# 7_Power_Supply.net
KiCad netlist of a schematic drawn in Altium Designer
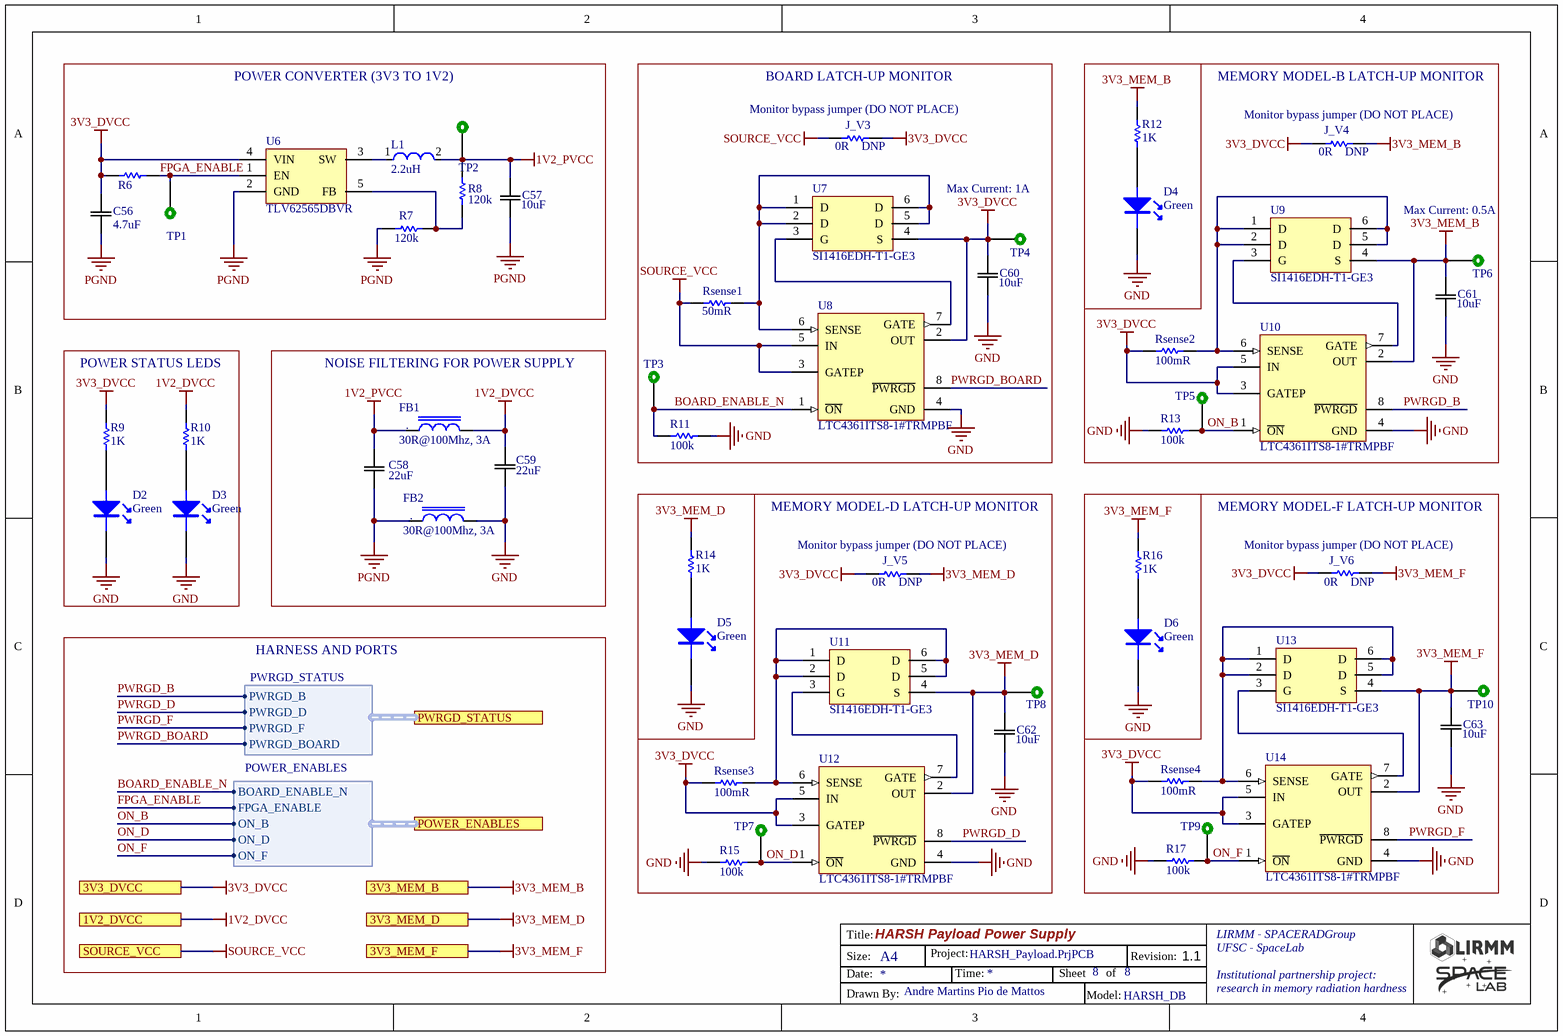
[diagram p0: 7_Power_Supply.SchDoc]

(export (version "E")
  (design (tool "Eeschema 10.0.6"))
  (components
    (comp (ref "C56")
      (value "4.7uF")
      (footprint "DONE_C0603")
      (description "CAP CER 4.7UF 10V 10% X5R 0603")
      (fields (field (name "PARTNUMBER") "C0603C475K8PACTU") (field (name "VOLTAGE") "10V"))
      (libsource (lib "HARSH_Payload_SchLib") (part "DONE_CAP_4.7uF_0603_X5R"))
    )
    (comp (ref "C57")
      (value "10uF")
      (footprint "DONE_C0603")
      (description "CAP CER 10uF 16V 0603 X5R")
      (fields
        (field (name "PARTNUMBER") "GRM188R61C106KAALD")
        (field (name "MANUFACTURER") "Murata")
        (field (name "CAPACITANCE") "10uF")
      )
      (libsource (lib "HARSH_Payload_SchLib") (part "DONE_CAP_10uF_0603_X5R"))
    )
    (comp (ref "C58")
      (value "22uF")
      (footprint "DONE_C0603")
      (description "CAP CER 22UF 10V X5R 0603")
      (fields (field (name "PARTNUMBER") "CL10A226MPCNUBE") (field (name "CAPACITANCE") "22uF"))
      (libsource (lib "HARSH_Payload_SchLib") (part "DONE_CAP_22uF_0603_X5R"))
    )
    (comp (ref "C59")
      (value "22uF")
      (footprint "DONE_C0603")
      (description "CAP CER 22UF 10V X5R 0603")
      (fields (field (name "PARTNUMBER") "CL10A226MPCNUBE") (field (name "CAPACITANCE") "22uF"))
      (libsource (lib "HARSH_Payload_SchLib") (part "DONE_CAP_22uF_0603_X5R"))
    )
    (comp (ref "C60")
      (value "10uF")
      (footprint "DONE_C0603")
      (description "CAP CER 10uF 16V 0603 X5R")
      (fields
        (field (name "PARTNUMBER") "GRM188R61C106KAALD")
        (field (name "MANUFACTURER") "Murata")
        (field (name "CAPACITANCE") "10uF")
      )
      (libsource (lib "HARSH_Payload_SchLib") (part "DONE_CAP_10uF_0603_X5R"))
    )
    (comp (ref "C61")
      (value "10uF")
      (footprint "DONE_C0603")
      (description "CAP CER 10uF 16V 0603 X5R")
      (fields
        (field (name "PARTNUMBER") "GRM188R61C106KAALD")
        (field (name "MANUFACTURER") "Murata")
        (field (name "CAPACITANCE") "10uF")
      )
      (libsource (lib "HARSH_Payload_SchLib") (part "DONE_CAP_10uF_0603_X5R"))
    )
    (comp (ref "C62")
      (value "10uF")
      (footprint "DONE_C0603")
      (description "CAP CER 10uF 16V 0603 X5R")
      (fields
        (field (name "PARTNUMBER") "GRM188R61C106KAALD")
        (field (name "MANUFACTURER") "Murata")
        (field (name "CAPACITANCE") "10uF")
      )
      (libsource (lib "HARSH_Payload_SchLib") (part "DONE_CAP_10uF_0603_X5R"))
    )
    (comp (ref "C63")
      (value "10uF")
      (footprint "DONE_C0603")
      (description "CAP CER 10uF 16V 0603 X5R")
      (fields
        (field (name "PARTNUMBER") "GRM188R61C106KAALD")
        (field (name "MANUFACTURER") "Murata")
        (field (name "CAPACITANCE") "10uF")
      )
      (libsource (lib "HARSH_Payload_SchLib") (part "DONE_CAP_10uF_0603_X5R"))
    )
    (comp (ref "D2")
      (value "Green")
      (footprint "DONE_D0603_GREEN")
      (description "SMD Green LED")
      (fields (field (name "PARTNUMBER") "HSMQ-C191-T0000"))
      (libsource (lib "HARSH_Payload_SchLib") (part "DONE_LED_GREEN_0603"))
    )
    (comp (ref "D3")
      (value "Green")
      (footprint "DONE_D0603_GREEN")
      (description "SMD Green LED")
      (fields (field (name "PARTNUMBER") "HSMQ-C191-T0000"))
      (libsource (lib "HARSH_Payload_SchLib") (part "DONE_LED_GREEN_0603"))
    )
    (comp (ref "D4")
      (value "Green")
      (footprint "DONE_D0603_GREEN")
      (description "SMD Green LED")
      (fields (field (name "PARTNUMBER") "HSMQ-C191-T0000"))
      (libsource (lib "HARSH_Payload_SchLib") (part "DONE_LED_GREEN_0603"))
    )
    (comp (ref "D5")
      (value "Green")
      (footprint "DONE_D0603_GREEN")
      (description "SMD Green LED")
      (fields (field (name "PARTNUMBER") "HSMQ-C191-T0000"))
      (libsource (lib "HARSH_Payload_SchLib") (part "DONE_LED_GREEN_0603"))
    )
    (comp (ref "D6")
      (value "Green")
      (footprint "DONE_D0603_GREEN")
      (description "SMD Green LED")
      (fields (field (name "PARTNUMBER") "HSMQ-C191-T0000"))
      (libsource (lib "HARSH_Payload_SchLib") (part "DONE_LED_GREEN_0603"))
    )
    (comp (ref "FB1")
      (value "30R@100Mhz, 3A")
      (footprint "DONE_L0805")
      (description "Ferrite Bead 30 OHM 3A 100MHz")
      (fields (field (name "PARTNUMBER") "BLM21PG300SN1D"))
      (libsource (lib "HARSH_Payload_SchLib") (part "DONE_FB_30R_3A_100MHz_0805"))
    )
    (comp (ref "FB2")
      (value "30R@100Mhz, 3A")
      (footprint "DONE_L0805")
      (description "Ferrite Bead 30 OHM 3A 100MHz")
      (fields (field (name "PARTNUMBER") "BLM21PG300SN1D"))
      (libsource (lib "HARSH_Payload_SchLib") (part "DONE_FB_30R_3A_100MHz_0805"))
    )
    (comp (ref "J_V3")
      (value "0R")
      (footprint "DONE_R0603")
      (description "RES SMD 0 OHM JUMPER 1/10W 0603")
      (fields (field (name "PARTNUMBER") "RC0603JR-070RL"))
      (libsource (lib "HARSH_Payload_SchLib") (part "DONE_RES_0R_0603"))
    )
    (comp (ref "J_V4")
      (value "0R")
      (footprint "DONE_R0603")
      (description "RES SMD 0 OHM JUMPER 1/10W 0603")
      (fields (field (name "PARTNUMBER") "RC0603JR-070RL"))
      (libsource (lib "HARSH_Payload_SchLib") (part "DONE_RES_0R_0603"))
    )
    (comp (ref "J_V5")
      (value "0R")
      (footprint "DONE_R0603")
      (description "RES SMD 0 OHM JUMPER 1/10W 0603")
      (fields (field (name "PARTNUMBER") "RC0603JR-070RL"))
      (libsource (lib "HARSH_Payload_SchLib") (part "DONE_RES_0R_0603"))
    )
    (comp (ref "J_V6")
      (value "0R")
      (footprint "DONE_R0603")
      (description "RES SMD 0 OHM JUMPER 1/10W 0603")
      (fields (field (name "PARTNUMBER") "RC0603JR-070RL"))
      (libsource (lib "HARSH_Payload_SchLib") (part "DONE_RES_0R_0603"))
    )
    (comp (ref "L1")
      (value "2.2uH")
      (footprint "DONE_IND_2.2uH")
      (description "Inductor Power Chip Shielded Wirewound 2.2uH 20% 1MHz Ferrite 1.8A 0.0588Ohm DCR 1515 T/R")
      (fields (field (name "PARTNUMBER") "LQH44PN2R2MP0L") (field (name "Comment") "DONE_IND_2.2uH"))
      (libsource (lib "HARSH_Payload_SchLib") (part "DONE_IND_2.2uH"))
    )
    (comp (ref "R6")
      (value "10k")
      (footprint "DONE_R0603")
      (description "1/8W 1%  0603 10K")
      (fields
        (field (name "PARTNUMBER") "MCT0603MC1002FP500")
        (field (name "MANUFACTURER") "Vishay Beyschlag")
      )
      (libsource (lib "HARSH_Payload_SchLib") (part "DONE_RES_10K_0603"))
    )
    (comp (ref "R7")
      (value "120k")
      (footprint "DONE_R0603")
      (description "1/10W 1%  0603")
      (fields
        (field (name "PARTNUMBER") "CRCW0603120KFKEAC")
        (field (name "MANUFACTURER") "Vishay Beyschlag")
        (field (name "RESISTANCE") "120k")
      )
      (libsource (lib "HARSH_Payload_SchLib") (part "DONE_RES_120K_0603"))
    )
    (comp (ref "R8")
      (value "120k")
      (footprint "DONE_R0603")
      (description "1/10W 1%  0603")
      (fields
        (field (name "PARTNUMBER") "CRCW0603120KFKEAC")
        (field (name "MANUFACTURER") "Vishay Beyschlag")
        (field (name "RESISTANCE") "120k")
      )
      (libsource (lib "HARSH_Payload_SchLib") (part "DONE_RES_120K_0603"))
    )
    (comp (ref "R9")
      (value "1K")
      (footprint "DONE_R0603")
      (description "RES SMD 1K OHM 1% 1/4W 0603")
      (fields
        (field (name "MANUFACTURER") "Rohm")
        (field (name "MANUFACTURER PART NUMBER") "ESR03EZPF1001")
        (field (name "RESISTANCE") "1K")
      )
      (libsource (lib "HARSH_Payload_SchLib") (part "DONE_RES_1K_0603"))
    )
    (comp (ref "R10")
      (value "1K")
      (footprint "DONE_R0603")
      (description "RES SMD 1K OHM 1% 1/4W 0603")
      (fields
        (field (name "MANUFACTURER") "Rohm")
        (field (name "MANUFACTURER PART NUMBER") "ESR03EZPF1001")
        (field (name "RESISTANCE") "1K")
      )
      (libsource (lib "HARSH_Payload_SchLib") (part "DONE_RES_1K_0603"))
    )
    (comp (ref "R11")
      (value "100k")
      (footprint "DONE_R0805")
      (description "RES 100K OHM 1/8W 1% 0805")
      (fields
        (field (name "PARTNUMBER") "AC0805FR-13100KL")
        (field (name "MANUFACTURER") "Yageo")
        (field (name "RESISTANCE") "100k")
      )
      (libsource (lib "HARSH_Payload_SchLib") (part "DONE_RES_100k_0805"))
    )
    (comp (ref "R12")
      (value "1K")
      (footprint "DONE_R0603")
      (description "RES SMD 1K OHM 1% 1/4W 0603")
      (fields
        (field (name "MANUFACTURER") "Rohm")
        (field (name "MANUFACTURER PART NUMBER") "ESR03EZPF1001")
        (field (name "RESISTANCE") "1K")
      )
      (libsource (lib "HARSH_Payload_SchLib") (part "DONE_RES_1K_0603"))
    )
    (comp (ref "R13")
      (value "100k")
      (footprint "DONE_R0805")
      (description "RES 100K OHM 1/8W 1% 0805")
      (fields
        (field (name "PARTNUMBER") "AC0805FR-13100KL")
        (field (name "MANUFACTURER") "Yageo")
        (field (name "RESISTANCE") "100k")
      )
      (libsource (lib "HARSH_Payload_SchLib") (part "DONE_RES_100k_0805"))
    )
    (comp (ref "R14")
      (value "1K")
      (footprint "DONE_R0603")
      (description "RES SMD 1K OHM 1% 1/4W 0603")
      (fields
        (field (name "MANUFACTURER") "Rohm")
        (field (name "MANUFACTURER PART NUMBER") "ESR03EZPF1001")
        (field (name "RESISTANCE") "1K")
      )
      (libsource (lib "HARSH_Payload_SchLib") (part "DONE_RES_1K_0603"))
    )
    (comp (ref "R15")
      (value "100k")
      (footprint "DONE_R0805")
      (description "RES 100K OHM 1/8W 1% 0805")
      (fields
        (field (name "PARTNUMBER") "AC0805FR-13100KL")
        (field (name "MANUFACTURER") "Yageo")
        (field (name "RESISTANCE") "100k")
      )
      (libsource (lib "HARSH_Payload_SchLib") (part "DONE_RES_100k_0805"))
    )
    (comp (ref "R16")
      (value "1K")
      (footprint "DONE_R0603")
      (description "RES SMD 1K OHM 1% 1/4W 0603")
      (fields
        (field (name "MANUFACTURER") "Rohm")
        (field (name "MANUFACTURER PART NUMBER") "ESR03EZPF1001")
        (field (name "RESISTANCE") "1K")
      )
      (libsource (lib "HARSH_Payload_SchLib") (part "DONE_RES_1K_0603"))
    )
    (comp (ref "R17")
      (value "100k")
      (footprint "DONE_R0805")
      (description "RES 100K OHM 1/8W 1% 0805")
      (fields
        (field (name "PARTNUMBER") "AC0805FR-13100KL")
        (field (name "MANUFACTURER") "Yageo")
        (field (name "RESISTANCE") "100k")
      )
      (libsource (lib "HARSH_Payload_SchLib") (part "DONE_RES_100k_0805"))
    )
    (comp (ref "Rsense1")
      (value "0.05R")
      (footprint "DONE_R0603")
      (description "RES 0.05 OHM 1% 1/3W 0603")
      (fields (field (name "PARTNUMBER") "ERJ-3BWFR050V") (field (name "RESISTANCE") "50mR"))
      (libsource (lib "HARSH_Payload_SchLib") (part "DONE_RES_0.05R_0603"))
    )
    (comp (ref "Rsense2")
      (value "0.1")
      (footprint "DONE_R0603")
      (description "RES 100 OHM 1% 1/8W 0603")
      (fields (field (name "RESISTANCE") "100mR") (field (name "PARTNUMBER") "RNCP0603FTD100R"))
      (libsource (lib "HARSH_Payload_SchLib") (part "DONE_RES_0.1R_0603"))
    )
    (comp (ref "Rsense3")
      (value "0.1")
      (footprint "DONE_R0603")
      (description "RES 100 OHM 1% 1/8W 0603")
      (fields (field (name "RESISTANCE") "100mR") (field (name "PARTNUMBER") "RNCP0603FTD100R"))
      (libsource (lib "HARSH_Payload_SchLib") (part "DONE_RES_0.1R_0603"))
    )
    (comp (ref "Rsense4")
      (value "0.1")
      (footprint "DONE_R0603")
      (description "RES 100 OHM 1% 1/8W 0603")
      (fields (field (name "RESISTANCE") "100mR") (field (name "PARTNUMBER") "RNCP0603FTD100R"))
      (libsource (lib "HARSH_Payload_SchLib") (part "DONE_RES_0.1R_0603"))
    )
    (comp (ref "TP1")
      (value "TEST_POINT")
      (footprint "DONE_TEST_POINT")
      (description "Test point")
      (libsource (lib "HARSH_Payload_SchLib") (part "DONE_TEST_POINT"))
    )
    (comp (ref "TP2")
      (value "TEST_POINT")
      (footprint "DONE_TEST_POINT")
      (description "Test point")
      (libsource (lib "HARSH_Payload_SchLib") (part "DONE_TEST_POINT"))
    )
    (comp (ref "TP3")
      (value "TEST_POINT")
      (footprint "DONE_TEST_POINT")
      (description "Test point")
      (libsource (lib "HARSH_Payload_SchLib") (part "DONE_TEST_POINT"))
    )
    (comp (ref "TP4")
      (value "TEST_POINT")
      (footprint "DONE_TEST_POINT")
      (description "Test point")
      (libsource (lib "HARSH_Payload_SchLib") (part "DONE_TEST_POINT"))
    )
    (comp (ref "TP5")
      (value "TEST_POINT")
      (footprint "DONE_TEST_POINT")
      (description "Test point")
      (libsource (lib "HARSH_Payload_SchLib") (part "DONE_TEST_POINT"))
    )
    (comp (ref "TP6")
      (value "TEST_POINT")
      (footprint "DONE_TEST_POINT")
      (description "Test point")
      (libsource (lib "HARSH_Payload_SchLib") (part "DONE_TEST_POINT"))
    )
    (comp (ref "TP7")
      (value "TEST_POINT")
      (footprint "DONE_TEST_POINT")
      (description "Test point")
      (libsource (lib "HARSH_Payload_SchLib") (part "DONE_TEST_POINT"))
    )
    (comp (ref "TP8")
      (value "TEST_POINT")
      (footprint "DONE_TEST_POINT")
      (description "Test point")
      (libsource (lib "HARSH_Payload_SchLib") (part "DONE_TEST_POINT"))
    )
    (comp (ref "TP9")
      (value "TEST_POINT")
      (footprint "DONE_TEST_POINT")
      (description "Test point")
      (libsource (lib "HARSH_Payload_SchLib") (part "DONE_TEST_POINT"))
    )
    (comp (ref "TP10")
      (value "TEST_POINT")
      (footprint "DONE_TEST_POINT")
      (description "Test point")
      (libsource (lib "HARSH_Payload_SchLib") (part "DONE_TEST_POINT"))
    )
    (comp (ref "U6")
      (value "TLV62565DBVR")
      (footprint "DONE_SOT23_5")
      (description "IC REG BUCK ADJ 1.5A SOT23-5")
      (fields (field (name "MANUFACTURER") "Texas Instruments") (field (name "PARTNUMBER") "TLV62565DBVR"))
      (libsource (lib "HARSH_Payload_SchLib") (part "DONE_TLV62565DBVR"))
    )
    (comp (ref "U7")
      (value "SI1416EDH-T1-GE3")
      (footprint "DONE_SOT363_6")
      (description "MOSFET 30V Vds 12V Vgs SC70-6 SOT-363-6")
      (fields (field (name "MANUFACTURER") "Vishay") (field (name "PARTNUMBER") "SI1416EDH-T1-GE3"))
      (libsource (lib "HARSH_Payload_SchLib") (part "DONE_SI1416EDH-T1-GE3"))
    )
    (comp (ref "U8")
      (value "LTC4361ITS8-1#TRMPBF")
      (footprint "DONE_TSOT_23_8")
      (fields
        (field (name "MANUFACTURER") "Linear Technology")
        (field (name "PARTNUMBER") "LTC4361ITS8-1#TRMPBF")
      )
      (libsource (lib "HARSH_Payload_SchLib") (part "DONE_LTC4361ITS8-1"))
    )
    (comp (ref "U9")
      (value "SI1416EDH-T1-GE3")
      (footprint "DONE_SOT363_6")
      (description "MOSFET 30V Vds 12V Vgs SC70-6 SOT-363-6")
      (fields (field (name "MANUFACTURER") "Vishay") (field (name "PARTNUMBER") "SI1416EDH-T1-GE3"))
      (libsource (lib "HARSH_Payload_SchLib") (part "DONE_SI1416EDH-T1-GE3"))
    )
    (comp (ref "U10")
      (value "LTC4361ITS8-1#TRMPBF")
      (footprint "DONE_TSOT_23_8")
      (fields
        (field (name "MANUFACTURER") "Linear Technology")
        (field (name "PARTNUMBER") "LTC4361ITS8-1#TRMPBF")
      )
      (libsource (lib "HARSH_Payload_SchLib") (part "DONE_LTC4361ITS8-1"))
    )
    (comp (ref "U11")
      (value "SI1416EDH-T1-GE3")
      (footprint "DONE_SOT363_6")
      (description "MOSFET 30V Vds 12V Vgs SC70-6 SOT-363-6")
      (fields (field (name "MANUFACTURER") "Vishay") (field (name "PARTNUMBER") "SI1416EDH-T1-GE3"))
      (libsource (lib "HARSH_Payload_SchLib") (part "DONE_SI1416EDH-T1-GE3"))
    )
    (comp (ref "U12")
      (value "LTC4361ITS8-1#TRMPBF")
      (footprint "DONE_TSOT_23_8")
      (fields
        (field (name "MANUFACTURER") "Linear Technology")
        (field (name "PARTNUMBER") "LTC4361ITS8-1#TRMPBF")
      )
      (libsource (lib "HARSH_Payload_SchLib") (part "DONE_LTC4361ITS8-1"))
    )
    (comp (ref "U13")
      (value "SI1416EDH-T1-GE3")
      (footprint "DONE_SOT363_6")
      (description "MOSFET 30V Vds 12V Vgs SC70-6 SOT-363-6")
      (fields (field (name "MANUFACTURER") "Vishay") (field (name "PARTNUMBER") "SI1416EDH-T1-GE3"))
      (libsource (lib "HARSH_Payload_SchLib") (part "DONE_SI1416EDH-T1-GE3"))
    )
    (comp (ref "U14")
      (value "LTC4361ITS8-1#TRMPBF")
      (footprint "DONE_TSOT_23_8")
      (fields
        (field (name "MANUFACTURER") "Linear Technology")
        (field (name "PARTNUMBER") "LTC4361ITS8-1#TRMPBF")
      )
      (libsource (lib "HARSH_Payload_SchLib") (part "DONE_LTC4361ITS8-1"))
    )
  )
  (nets
    (net (code "3") (name "/BOARD_ENABLE_N") (class "Default")
      (node (ref "R11") (pin "2") (pinfunction "2_2") (pintype "passive"))
      (node (ref "TP3") (pin "1") (pinfunction "1_1") (pintype "passive"))
      (node (ref "U8") (pin "1") (pinfunction "~{ON}_1") (pintype "input"))
    )
    (net (code "4") (name "/FPGA_ENABLE") (class "Default")
      (node (ref "R6") (pin "1") (pinfunction "1_1") (pintype "passive"))
      (node (ref "TP1") (pin "1") (pinfunction "1_1") (pintype "passive"))
      (node (ref "U6") (pin "1") (pinfunction "EN_1") (pintype "passive"))
    )
    (net (code "5") (name "/ON_B") (class "Default")
      (node (ref "R13") (pin "1") (pinfunction "1_1") (pintype "passive"))
      (node (ref "TP5") (pin "1") (pinfunction "1_1") (pintype "passive"))
      (node (ref "U10") (pin "1") (pinfunction "~{ON}_1") (pintype "input"))
    )
    (net (code "6") (name "/ON_D") (class "Default")
      (node (ref "R15") (pin "1") (pinfunction "1_1") (pintype "passive"))
      (node (ref "TP7") (pin "1") (pinfunction "1_1") (pintype "passive"))
      (node (ref "U12") (pin "1") (pinfunction "~{ON}_1") (pintype "input"))
    )
    (net (code "7") (name "/ON_F") (class "Default")
      (node (ref "R17") (pin "1") (pinfunction "1_1") (pintype "passive"))
      (node (ref "TP9") (pin "1") (pinfunction "1_1") (pintype "passive"))
      (node (ref "U14") (pin "1") (pinfunction "~{ON}_1") (pintype "input"))
    )
    (net (code "8") (name "/PWRGD_B") (class "Default")
      (node (ref "U10") (pin "8") (pinfunction "~{PWRGD}_8") (pintype "tri_state"))
    )
    (net (code "9") (name "/PWRGD_BOARD") (class "Default")
      (node (ref "U8") (pin "8") (pinfunction "~{PWRGD}_8") (pintype "tri_state"))
    )
    (net (code "10") (name "/PWRGD_D") (class "Default")
      (node (ref "U12") (pin "8") (pinfunction "~{PWRGD}_8") (pintype "tri_state"))
    )
    (net (code "11") (name "/PWRGD_F") (class "Default")
      (node (ref "U14") (pin "8") (pinfunction "~{PWRGD}_8") (pintype "tri_state"))
    )
    (net (code "14") (name "1V2_DVCC") (class "Default")
      (node (ref "C59") (pin "1") (pinfunction "1_1") (pintype "passive"))
      (node (ref "FB1") (pin "2") (pinfunction "2_2") (pintype "passive"))
      (node (ref "R10") (pin "2") (pinfunction "2_2") (pintype "passive"))
    )
    (net (code "15") (name "1V2_PVCC") (class "Default")
      (node (ref "C57") (pin "1") (pinfunction "1_1") (pintype "passive"))
      (node (ref "C58") (pin "1") (pinfunction "1_1") (pintype "passive"))
      (node (ref "FB1") (pin "1") (pinfunction "1_1") (pintype "passive"))
      (node (ref "L1") (pin "2") (pinfunction "2_2") (pintype "passive"))
      (node (ref "R8") (pin "2") (pinfunction "2_2") (pintype "passive"))
      (node (ref "TP2") (pin "1") (pinfunction "1_1") (pintype "passive"))
    )
    (net (code "16") (name "3V3_DVCC") (class "Default")
      (node (ref "C56") (pin "1") (pinfunction "1_1") (pintype "passive"))
      (node (ref "C60") (pin "1") (pinfunction "1_1") (pintype "passive"))
      (node (ref "J_V3") (pin "1") (pinfunction "1_1") (pintype "passive"))
      (node (ref "J_V4") (pin "2") (pinfunction "2_2") (pintype "passive"))
      (node (ref "J_V5") (pin "2") (pinfunction "2_2") (pintype "passive"))
      (node (ref "J_V6") (pin "2") (pinfunction "2_2") (pintype "passive"))
      (node (ref "R6") (pin "2") (pinfunction "2_2") (pintype "passive"))
      (node (ref "R9") (pin "2") (pinfunction "2_2") (pintype "passive"))
      (node (ref "Rsense2") (pin "2") (pinfunction "2_2") (pintype "passive"))
      (node (ref "Rsense3") (pin "2") (pinfunction "2_2") (pintype "passive"))
      (node (ref "Rsense4") (pin "2") (pinfunction "2_2") (pintype "passive"))
      (node (ref "TP4") (pin "1") (pinfunction "1_1") (pintype "passive"))
      (node (ref "U10") (pin "3") (pinfunction "GATEP_3") (pintype "passive"))
      (node (ref "U10") (pin "5") (pinfunction "IN_5") (pintype "power_in"))
      (node (ref "U12") (pin "3") (pinfunction "GATEP_3") (pintype "passive"))
      (node (ref "U12") (pin "5") (pinfunction "IN_5") (pintype "power_in"))
      (node (ref "U14") (pin "3") (pinfunction "GATEP_3") (pintype "passive"))
      (node (ref "U14") (pin "5") (pinfunction "IN_5") (pintype "power_in"))
      (node (ref "U6") (pin "4") (pinfunction "VIN_4") (pintype "passive"))
      (node (ref "U7") (pin "4") (pinfunction "S_4") (pintype "passive"))
      (node (ref "U8") (pin "2") (pinfunction "OUT_2") (pintype "passive"))
    )
    (net (code "17") (name "3V3_MEM_B") (class "Default")
      (node (ref "C61") (pin "1") (pinfunction "1_1") (pintype "passive"))
      (node (ref "J_V4") (pin "1") (pinfunction "1_1") (pintype "passive"))
      (node (ref "R12") (pin "2") (pinfunction "2_2") (pintype "passive"))
      (node (ref "TP6") (pin "1") (pinfunction "1_1") (pintype "passive"))
      (node (ref "U10") (pin "2") (pinfunction "OUT_2") (pintype "passive"))
      (node (ref "U9") (pin "4") (pinfunction "S_4") (pintype "passive"))
    )
    (net (code "18") (name "3V3_MEM_D") (class "Default")
      (node (ref "C62") (pin "1") (pinfunction "1_1") (pintype "passive"))
      (node (ref "J_V5") (pin "1") (pinfunction "1_1") (pintype "passive"))
      (node (ref "R14") (pin "2") (pinfunction "2_2") (pintype "passive"))
      (node (ref "TP8") (pin "1") (pinfunction "1_1") (pintype "passive"))
      (node (ref "U11") (pin "4") (pinfunction "S_4") (pintype "passive"))
      (node (ref "U12") (pin "2") (pinfunction "OUT_2") (pintype "passive"))
    )
    (net (code "19") (name "3V3_MEM_F") (class "Default")
      (node (ref "C63") (pin "1") (pinfunction "1_1") (pintype "passive"))
      (node (ref "J_V6") (pin "1") (pinfunction "1_1") (pintype "passive"))
      (node (ref "R16") (pin "2") (pinfunction "2_2") (pintype "passive"))
      (node (ref "TP10") (pin "1") (pinfunction "1_1") (pintype "passive"))
      (node (ref "U13") (pin "4") (pinfunction "S_4") (pintype "passive"))
      (node (ref "U14") (pin "2") (pinfunction "OUT_2") (pintype "passive"))
    )
    (net (code "20") (name "GND") (class "Default")
      (node (ref "C59") (pin "2") (pinfunction "2_2") (pintype "passive"))
      (node (ref "C60") (pin "2") (pinfunction "2_2") (pintype "passive"))
      (node (ref "C61") (pin "2") (pinfunction "2_2") (pintype "passive"))
      (node (ref "C62") (pin "2") (pinfunction "2_2") (pintype "passive"))
      (node (ref "C63") (pin "2") (pinfunction "2_2") (pintype "passive"))
      (node (ref "D2") (pin "2") (pinfunction "K_2") (pintype "passive"))
      (node (ref "D3") (pin "2") (pinfunction "K_2") (pintype "passive"))
      (node (ref "D4") (pin "2") (pinfunction "K_2") (pintype "passive"))
      (node (ref "D5") (pin "2") (pinfunction "K_2") (pintype "passive"))
      (node (ref "D6") (pin "2") (pinfunction "K_2") (pintype "passive"))
      (node (ref "FB2") (pin "2") (pinfunction "2_2") (pintype "passive"))
      (node (ref "R11") (pin "1") (pinfunction "1_1") (pintype "passive"))
      (node (ref "R13") (pin "2") (pinfunction "2_2") (pintype "passive"))
      (node (ref "R15") (pin "2") (pinfunction "2_2") (pintype "passive"))
      (node (ref "R17") (pin "2") (pinfunction "2_2") (pintype "passive"))
      (node (ref "U10") (pin "4") (pinfunction "GND_4") (pintype "power_in"))
      (node (ref "U12") (pin "4") (pinfunction "GND_4") (pintype "power_in"))
      (node (ref "U14") (pin "4") (pinfunction "GND_4") (pintype "power_in"))
      (node (ref "U8") (pin "4") (pinfunction "GND_4") (pintype "power_in"))
    )
    (net (code "21") (name "Net-(D2-A)") (class "Default")
      (node (ref "D2") (pin "1") (pinfunction "A_1") (pintype "passive"))
      (node (ref "R9") (pin "1") (pinfunction "1_1") (pintype "passive"))
    )
    (net (code "22") (name "Net-(D3-A)") (class "Default")
      (node (ref "D3") (pin "1") (pinfunction "A_1") (pintype "passive"))
      (node (ref "R10") (pin "1") (pinfunction "1_1") (pintype "passive"))
    )
    (net (code "23") (name "Net-(D4-A)") (class "Default")
      (node (ref "D4") (pin "1") (pinfunction "A_1") (pintype "passive"))
      (node (ref "R12") (pin "1") (pinfunction "1_1") (pintype "passive"))
    )
    (net (code "24") (name "Net-(D5-A)") (class "Default")
      (node (ref "D5") (pin "1") (pinfunction "A_1") (pintype "passive"))
      (node (ref "R14") (pin "1") (pinfunction "1_1") (pintype "passive"))
    )
    (net (code "25") (name "Net-(D6-A)") (class "Default")
      (node (ref "D6") (pin "1") (pinfunction "A_1") (pintype "passive"))
      (node (ref "R16") (pin "1") (pinfunction "1_1") (pintype "passive"))
    )
    (net (code "26") (name "Net-(U6-FB)") (class "Default")
      (node (ref "R7") (pin "1") (pinfunction "1_1") (pintype "passive"))
      (node (ref "R8") (pin "1") (pinfunction "1_1") (pintype "passive"))
      (node (ref "U6") (pin "5") (pinfunction "FB_5") (pintype "passive"))
    )
    (net (code "27") (name "Net-(U6-SW)") (class "Default")
      (node (ref "L1") (pin "1") (pinfunction "1_1") (pintype "passive"))
      (node (ref "U6") (pin "3") (pinfunction "SW_3") (pintype "passive"))
    )
    (net (code "28") (name "Net-(U7-G)") (class "Default")
      (node (ref "U7") (pin "3") (pinfunction "G_3") (pintype "passive"))
      (node (ref "U8") (pin "7") (pinfunction "GATE_7") (pintype "output"))
    )
    (net (code "29") (name "Net-(U8-SENSE)") (class "Default")
      (node (ref "Rsense1") (pin "1") (pinfunction "1_1") (pintype "passive"))
      (node (ref "U7") (pin "1") (pinfunction "D_1") (pintype "passive"))
      (node (ref "U7") (pin "2") (pinfunction "D_2") (pintype "passive"))
      (node (ref "U7") (pin "5") (pinfunction "D_5") (pintype "passive"))
      (node (ref "U7") (pin "6") (pinfunction "D_6") (pintype "passive"))
      (node (ref "U8") (pin "6") (pinfunction "SENSE_6") (pintype "input"))
    )
    (net (code "30") (name "Net-(U10-GATE)") (class "Default")
      (node (ref "U10") (pin "7") (pinfunction "GATE_7") (pintype "output"))
      (node (ref "U9") (pin "3") (pinfunction "G_3") (pintype "passive"))
    )
    (net (code "31") (name "Net-(U10-SENSE)") (class "Default")
      (node (ref "Rsense2") (pin "1") (pinfunction "1_1") (pintype "passive"))
      (node (ref "U10") (pin "6") (pinfunction "SENSE_6") (pintype "input"))
      (node (ref "U9") (pin "1") (pinfunction "D_1") (pintype "passive"))
      (node (ref "U9") (pin "2") (pinfunction "D_2") (pintype "passive"))
      (node (ref "U9") (pin "5") (pinfunction "D_5") (pintype "passive"))
      (node (ref "U9") (pin "6") (pinfunction "D_6") (pintype "passive"))
    )
    (net (code "32") (name "Net-(U11-G)") (class "Default")
      (node (ref "U11") (pin "3") (pinfunction "G_3") (pintype "passive"))
      (node (ref "U12") (pin "7") (pinfunction "GATE_7") (pintype "output"))
    )
    (net (code "33") (name "Net-(U12-SENSE)") (class "Default")
      (node (ref "Rsense3") (pin "1") (pinfunction "1_1") (pintype "passive"))
      (node (ref "U11") (pin "1") (pinfunction "D_1") (pintype "passive"))
      (node (ref "U11") (pin "2") (pinfunction "D_2") (pintype "passive"))
      (node (ref "U11") (pin "5") (pinfunction "D_5") (pintype "passive"))
      (node (ref "U11") (pin "6") (pinfunction "D_6") (pintype "passive"))
      (node (ref "U12") (pin "6") (pinfunction "SENSE_6") (pintype "input"))
    )
    (net (code "34") (name "Net-(U13-G)") (class "Default")
      (node (ref "U13") (pin "3") (pinfunction "G_3") (pintype "passive"))
      (node (ref "U14") (pin "7") (pinfunction "GATE_7") (pintype "output"))
    )
    (net (code "35") (name "Net-(U14-SENSE)") (class "Default")
      (node (ref "Rsense4") (pin "1") (pinfunction "1_1") (pintype "passive"))
      (node (ref "U13") (pin "1") (pinfunction "D_1") (pintype "passive"))
      (node (ref "U13") (pin "2") (pinfunction "D_2") (pintype "passive"))
      (node (ref "U13") (pin "5") (pinfunction "D_5") (pintype "passive"))
      (node (ref "U13") (pin "6") (pinfunction "D_6") (pintype "passive"))
      (node (ref "U14") (pin "6") (pinfunction "SENSE_6") (pintype "input"))
    )
    (net (code "36") (name "PGND") (class "Default")
      (node (ref "C56") (pin "2") (pinfunction "2_2") (pintype "passive"))
      (node (ref "C57") (pin "2") (pinfunction "2_2") (pintype "passive"))
      (node (ref "C58") (pin "2") (pinfunction "2_2") (pintype "passive"))
      (node (ref "FB2") (pin "1") (pinfunction "1_1") (pintype "passive"))
      (node (ref "R7") (pin "2") (pinfunction "2_2") (pintype "passive"))
      (node (ref "U6") (pin "2") (pinfunction "GND_2") (pintype "passive"))
    )
    (net (code "37") (name "SOURCE_VCC") (class "Default")
      (node (ref "J_V3") (pin "2") (pinfunction "2_2") (pintype "passive"))
      (node (ref "Rsense1") (pin "2") (pinfunction "2_2") (pintype "passive"))
      (node (ref "U8") (pin "3") (pinfunction "GATEP_3") (pintype "passive"))
      (node (ref "U8") (pin "5") (pinfunction "IN_5") (pintype "power_in"))
    )
  )
)
